# Sheet2.net
KiCad netlist of a schematic drawn in Altium Designer
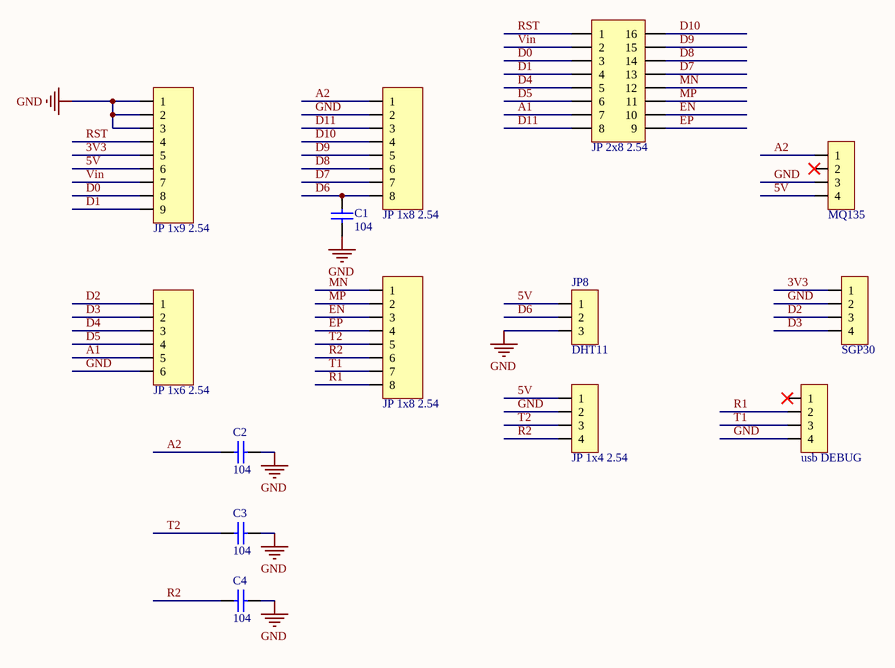
[diagram p0: Sheet2.SchDoc]

(export (version "E")
  (design (tool "Eeschema 10.0.6"))
  (components
    (comp (ref "C1")
      (value "104")
      (footprint "tu 0805")
      (description "Dán")
      (libsource (lib "Air_Logger_PCB") (part "Tu 0805 104 50V 10%"))
    )
    (comp (ref "C2")
      (value "104")
      (footprint "tu 0805")
      (description "Dán")
      (libsource (lib "Air_Logger_PCB") (part "Tu 0805 104 50V 10%"))
    )
    (comp (ref "C3")
      (value "104")
      (footprint "tu 0805")
      (description "Dán")
      (libsource (lib "Air_Logger_PCB") (part "Tu 0805 104 50V 10%"))
    )
    (comp (ref "C4")
      (value "104")
      (footprint "tu 0805")
      (description "Dán")
      (libsource (lib "Air_Logger_PCB") (part "Tu 0805 104 50V 10%"))
    )
    (comp (ref "JP1")
      (value "JP 2x8 2.54")
      (footprint "JP 2x8 DT")
      (description "Cắm")
      (libsource (lib "Jump") (part "JP 2x8 2.54 Duc Thang"))
    )
    (comp (ref "JP2")
      (value "JP 1x9 2.54")
      (footprint "JP 1x9 DT")
      (description "Cắm")
      (libsource (lib "Jump") (part "JP 1x9 2.54 Duc Thang"))
    )
    (comp (ref "JP3")
      (value "JP 1x8 2.54")
      (footprint "JP 1x8 DT")
      (description "Cắm")
      (libsource (lib "Jump") (part "JP 1x8 2.54 Duc Thang"))
    )
    (comp (ref "JP4")
      (value "MQ135")
      (footprint "JP 1x4 DT")
      (description "Cắm")
      (libsource (lib "Jump") (part "JP 1x4 2.54 Duc Thang"))
    )
    (comp (ref "JP5")
      (value "JP 1x8 2.54")
      (footprint "JP 1x8 DT")
      (description "Cắm")
      (libsource (lib "Jump") (part "JP 1x8 2.54 Duc Thang"))
    )
    (comp (ref "JP6")
      (value "SGP30")
      (footprint "JP 1x4 DT")
      (description "Cắm")
      (libsource (lib "Air_Logger_PCB") (part "JP 1x4 2.54 Duc Thang"))
    )
    (comp (ref "JP7")
      (value "JP 1x6 2.54")
      (footprint "JP 1x6 DT")
      (description "Cắm")
      (libsource (lib "Jump") (part "JP 1x6 2.54 Duc Thang"))
    )
    (comp (ref "JP8")
      (value "DHT11")
      (footprint "JP 1x3 DT")
      (description "Cắm")
      (libsource (lib "Air_Logger_PCB") (part "JP 1x3 2.54 Duc Thang_1"))
    )
    (comp (ref "JP9")
      (value "JP 1x4 2.54")
      (footprint "JP 1x4 DT")
      (description "Cắm")
      (libsource (lib "Air_Logger_PCB") (part "JP 1x4 2.54 Duc Thang"))
    )
    (comp (ref "JP10")
      (value "usb DEBUG")
      (footprint "JP 1x4 DT")
      (description "Cắm")
      (libsource (lib "Jump") (part "JP 1x4 2.54 Duc Thang"))
    )
  )
  (nets
    (net (code "1") (name "/3V3") (class "Default")
      (node (ref "JP2") (pin "5") (pinfunction "5_5") (pintype "passive"))
      (node (ref "JP6") (pin "1") (pinfunction "1_1") (pintype "passive"))
    )
    (net (code "2") (name "/5V") (class "Default")
      (node (ref "JP2") (pin "6") (pinfunction "6_6") (pintype "passive"))
      (node (ref "JP4") (pin "4") (pinfunction "4_4") (pintype "passive"))
      (node (ref "JP8") (pin "1") (pinfunction "1_1") (pintype "passive"))
      (node (ref "JP9") (pin "1") (pinfunction "1_1") (pintype "passive"))
    )
    (net (code "3") (name "/A1") (class "Default")
      (node (ref "JP1") (pin "7") (pinfunction "7_7") (pintype "passive"))
      (node (ref "JP7") (pin "5") (pinfunction "5_5") (pintype "passive"))
    )
    (net (code "4") (name "/A2") (class "Default")
      (node (ref "C2") (pin "2") (pinfunction "2_2") (pintype "passive"))
      (node (ref "JP3") (pin "1") (pinfunction "1_1") (pintype "passive"))
      (node (ref "JP4") (pin "1") (pinfunction "1_1") (pintype "passive"))
    )
    (net (code "5") (name "/D0") (class "Default")
      (node (ref "JP1") (pin "3") (pinfunction "3_3") (pintype "passive"))
      (node (ref "JP2") (pin "8") (pinfunction "8_8") (pintype "passive"))
    )
    (net (code "6") (name "/D1") (class "Default")
      (node (ref "JP1") (pin "4") (pinfunction "4_4") (pintype "passive"))
      (node (ref "JP2") (pin "9") (pinfunction "9_9") (pintype "passive"))
    )
    (net (code "7") (name "/D2") (class "Default")
      (node (ref "JP6") (pin "3") (pinfunction "3_3") (pintype "passive"))
      (node (ref "JP7") (pin "1") (pinfunction "1_1") (pintype "passive"))
    )
    (net (code "8") (name "/D3") (class "Default")
      (node (ref "JP6") (pin "4") (pinfunction "4_4") (pintype "passive"))
      (node (ref "JP7") (pin "2") (pinfunction "2_2") (pintype "passive"))
    )
    (net (code "9") (name "/D4") (class "Default")
      (node (ref "JP1") (pin "5") (pinfunction "5_5") (pintype "passive"))
      (node (ref "JP7") (pin "3") (pinfunction "3_3") (pintype "passive"))
    )
    (net (code "10") (name "/D5") (class "Default")
      (node (ref "JP1") (pin "6") (pinfunction "6_6") (pintype "passive"))
      (node (ref "JP7") (pin "4") (pinfunction "4_4") (pintype "passive"))
    )
    (net (code "11") (name "/D6") (class "Default")
      (node (ref "C1") (pin "1") (pinfunction "1_1") (pintype "passive"))
      (node (ref "JP3") (pin "8") (pinfunction "8_8") (pintype "passive"))
      (node (ref "JP8") (pin "2") (pinfunction "2_2") (pintype "passive"))
    )
    (net (code "12") (name "/D7") (class "Default")
      (node (ref "JP1") (pin "13") (pinfunction "13_13") (pintype "passive"))
      (node (ref "JP3") (pin "7") (pinfunction "7_7") (pintype "passive"))
    )
    (net (code "13") (name "/D8") (class "Default")
      (node (ref "JP1") (pin "14") (pinfunction "14_14") (pintype "passive"))
      (node (ref "JP3") (pin "6") (pinfunction "6_6") (pintype "passive"))
    )
    (net (code "14") (name "/D9") (class "Default")
      (node (ref "JP1") (pin "15") (pinfunction "15_15") (pintype "passive"))
      (node (ref "JP3") (pin "5") (pinfunction "5_5") (pintype "passive"))
    )
    (net (code "15") (name "/D10") (class "Default")
      (node (ref "JP1") (pin "16") (pinfunction "16_16") (pintype "passive"))
      (node (ref "JP3") (pin "4") (pinfunction "4_4") (pintype "passive"))
    )
    (net (code "16") (name "/D11") (class "Default")
      (node (ref "JP1") (pin "8") (pinfunction "8_8") (pintype "passive"))
      (node (ref "JP3") (pin "3") (pinfunction "3_3") (pintype "passive"))
    )
    (net (code "17") (name "/EN") (class "Default")
      (node (ref "JP1") (pin "10") (pinfunction "10_10") (pintype "passive"))
      (node (ref "JP5") (pin "3") (pinfunction "3_3") (pintype "passive"))
    )
    (net (code "18") (name "/EP") (class "Default")
      (node (ref "JP1") (pin "9") (pinfunction "9_9") (pintype "passive"))
      (node (ref "JP5") (pin "4") (pinfunction "4_4") (pintype "passive"))
    )
    (net (code "19") (name "/MN") (class "Default")
      (node (ref "JP1") (pin "12") (pinfunction "12_12") (pintype "passive"))
      (node (ref "JP5") (pin "1") (pinfunction "1_1") (pintype "passive"))
    )
    (net (code "20") (name "/MP") (class "Default")
      (node (ref "JP1") (pin "11") (pinfunction "11_11") (pintype "passive"))
      (node (ref "JP5") (pin "2") (pinfunction "2_2") (pintype "passive"))
    )
    (net (code "21") (name "/R1") (class "Default")
      (node (ref "JP10") (pin "2") (pinfunction "2_2") (pintype "passive"))
      (node (ref "JP5") (pin "8") (pinfunction "8_8") (pintype "passive"))
    )
    (net (code "22") (name "/R2") (class "Default")
      (node (ref "C4") (pin "2") (pinfunction "2_2") (pintype "passive"))
      (node (ref "JP5") (pin "6") (pinfunction "6_6") (pintype "passive"))
      (node (ref "JP9") (pin "4") (pinfunction "4_4") (pintype "passive"))
    )
    (net (code "23") (name "/RST") (class "Default")
      (node (ref "JP1") (pin "1") (pinfunction "1_1") (pintype "passive"))
      (node (ref "JP2") (pin "4") (pinfunction "4_4") (pintype "passive"))
    )
    (net (code "24") (name "/T1") (class "Default")
      (node (ref "JP10") (pin "3") (pinfunction "3_3") (pintype "passive"))
      (node (ref "JP5") (pin "7") (pinfunction "7_7") (pintype "passive"))
    )
    (net (code "25") (name "/T2") (class "Default")
      (node (ref "C3") (pin "2") (pinfunction "2_2") (pintype "passive"))
      (node (ref "JP5") (pin "5") (pinfunction "5_5") (pintype "passive"))
      (node (ref "JP9") (pin "3") (pinfunction "3_3") (pintype "passive"))
    )
    (net (code "26") (name "/Vin") (class "Default")
      (node (ref "JP1") (pin "2") (pinfunction "2_2") (pintype "passive"))
      (node (ref "JP2") (pin "7") (pinfunction "7_7") (pintype "passive"))
    )
    (net (code "27") (name "GND") (class "Default")
      (node (ref "C1") (pin "2") (pinfunction "2_2") (pintype "passive"))
      (node (ref "C2") (pin "1") (pinfunction "1_1") (pintype "passive"))
      (node (ref "C3") (pin "1") (pinfunction "1_1") (pintype "passive"))
      (node (ref "C4") (pin "1") (pinfunction "1_1") (pintype "passive"))
      (node (ref "JP10") (pin "4") (pinfunction "4_4") (pintype "passive"))
      (node (ref "JP2") (pin "1") (pinfunction "1_1") (pintype "passive"))
      (node (ref "JP2") (pin "2") (pinfunction "2_2") (pintype "passive"))
      (node (ref "JP2") (pin "3") (pinfunction "3_3") (pintype "passive"))
      (node (ref "JP3") (pin "2") (pinfunction "2_2") (pintype "passive"))
      (node (ref "JP4") (pin "3") (pinfunction "3_3") (pintype "passive"))
      (node (ref "JP6") (pin "2") (pinfunction "2_2") (pintype "passive"))
      (node (ref "JP7") (pin "6") (pinfunction "6_6") (pintype "passive"))
      (node (ref "JP8") (pin "3") (pinfunction "3_3") (pintype "passive"))
      (node (ref "JP9") (pin "2") (pinfunction "2_2") (pintype "passive"))
    )
    (net (code "28") (name "unconnected-(JP4-Pad2)") (class "Default")
      (node (ref "JP4") (pin "2") (pinfunction "2_2") (pintype "passive+no_connect"))
    )
    (net (code "29") (name "unconnected-(JP10-Pad1)") (class "Default")
      (node (ref "JP10") (pin "1") (pinfunction "1_1") (pintype "passive+no_connect"))
    )
  )
)
